# Transmitter_Schematic_Visualization.net
KiCad netlist of a schematic drawn in EAGLE
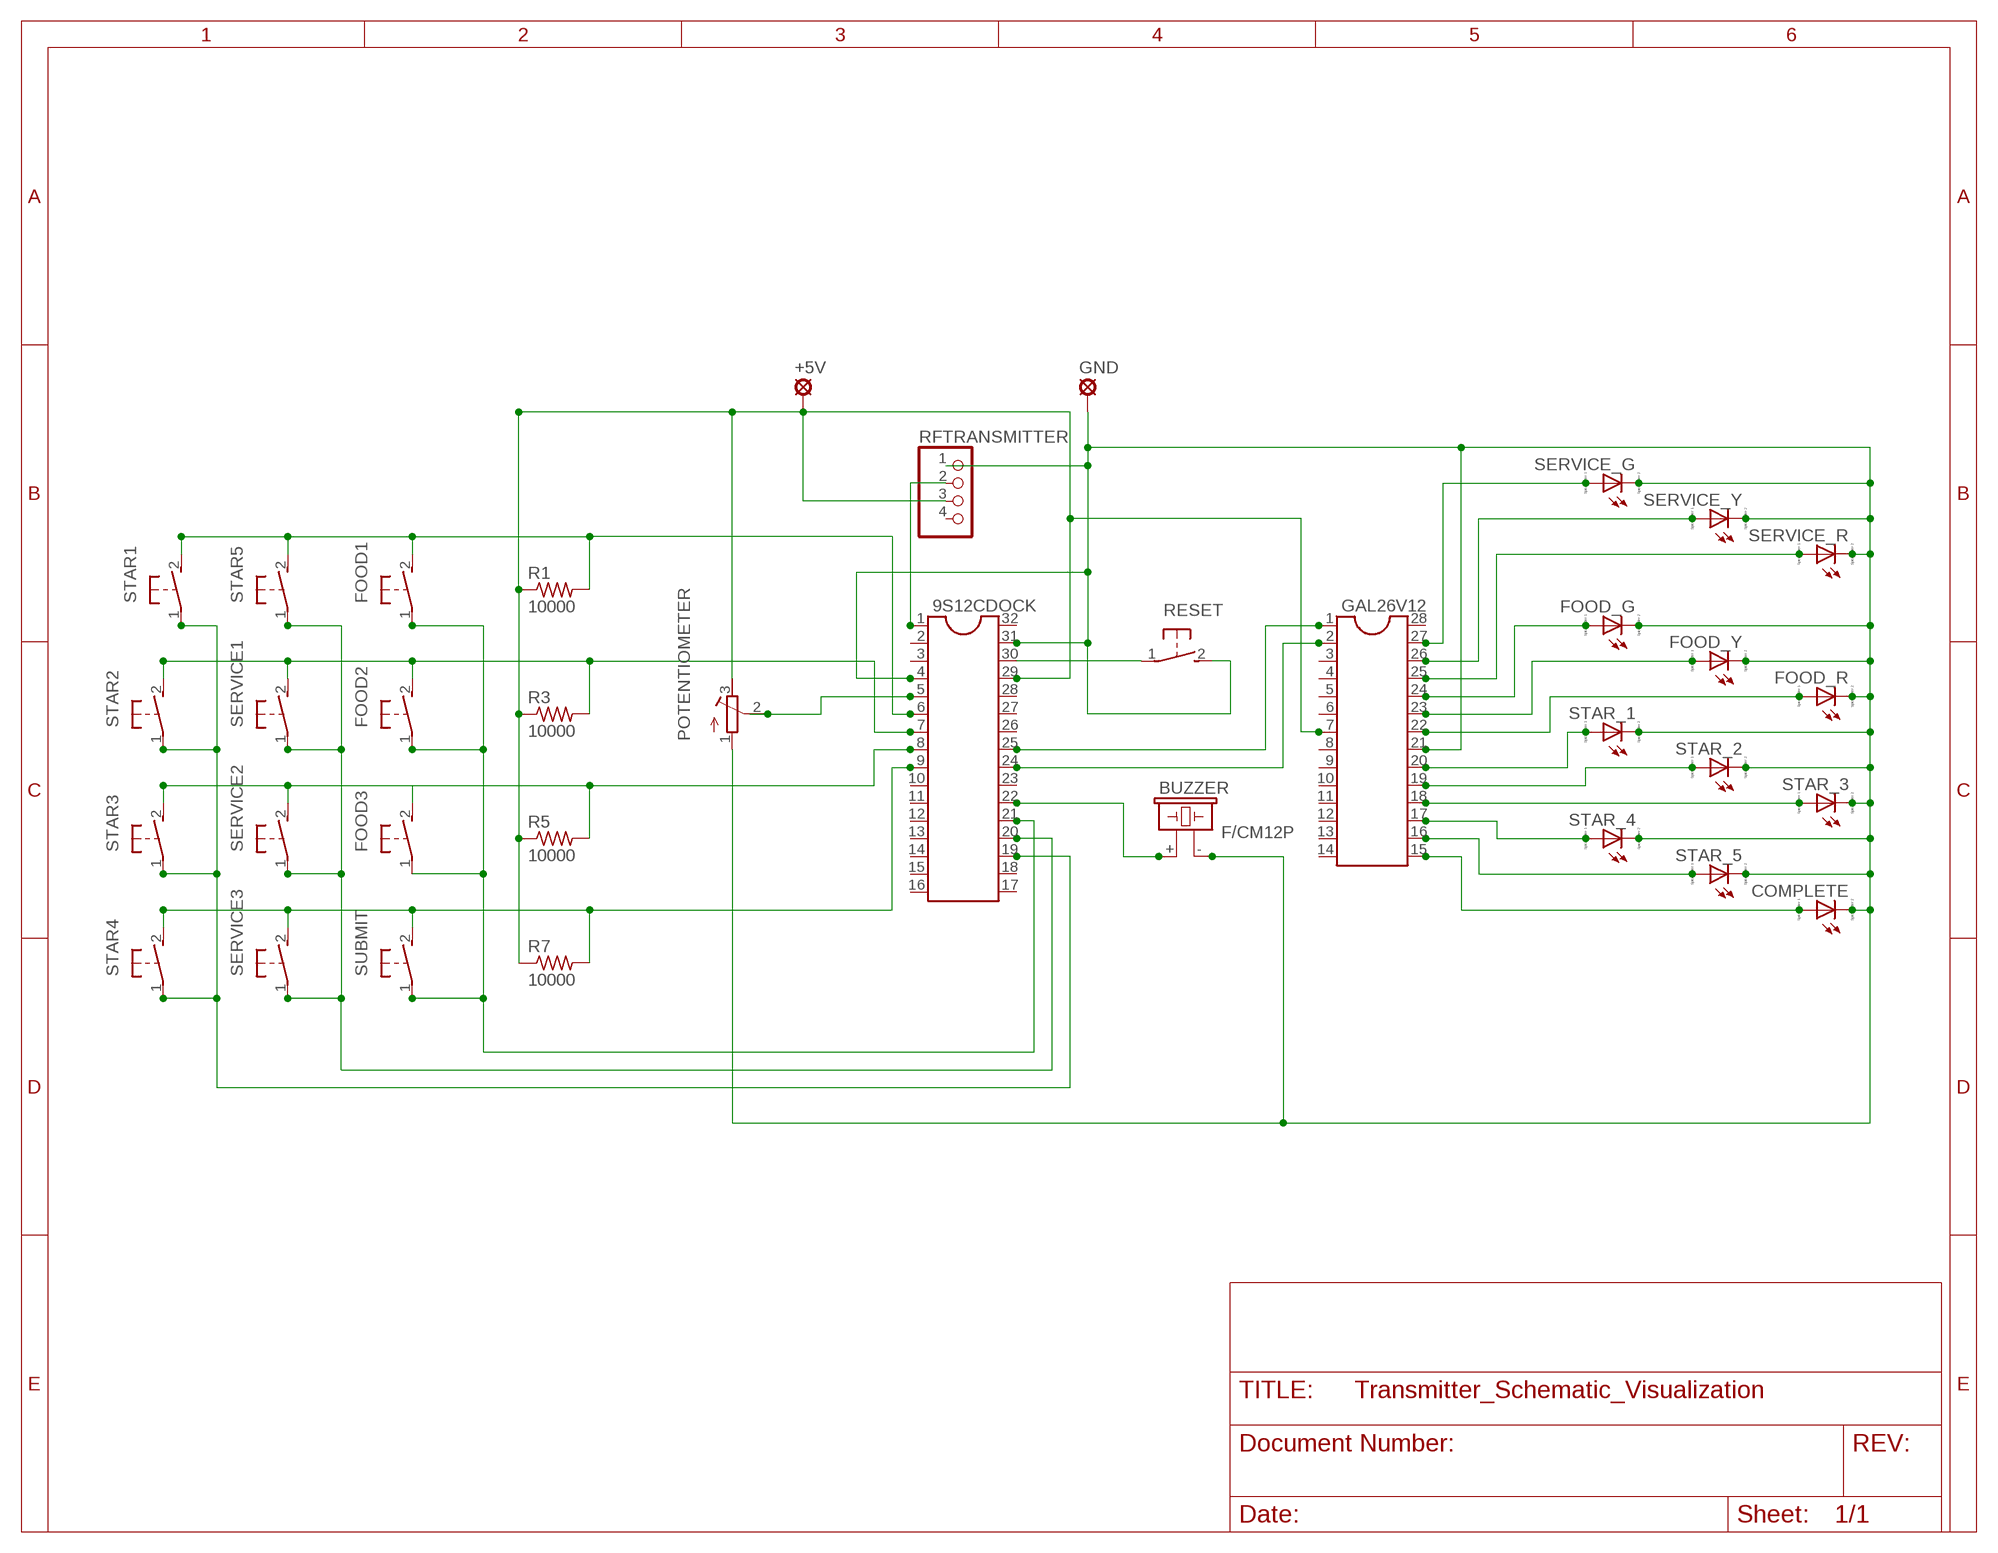
[diagram p0: schematic, sheet 1]

(export (version "E")
  (design (tool "Eeschema 10.0.6"))
  (components
    (comp (ref "+5V")
      (value "LSP10")
      (footprint "eagle-import:LSP10")
      (libsource (lib "eagle-import") (part "LSP10"))
    )
    (comp (ref "9S12CDOCK")
      (value "DIL32")
      (footprint "eagle-import:DIL32")
      (libsource (lib "eagle-import") (part "DIL32"))
    )
    (comp (ref "BUZZER")
      (value "F/CM12P")
      (footprint "eagle-import:F_CM12P")
      (libsource (lib "eagle-import") (part "F/CM12P"))
    )
    (comp (ref "COMPLETE")
      (value "LED_E")
      (footprint "eagle-import:LED_1206")
      (libsource (lib "eagle-import") (part "LED_E"))
    )
    (comp (ref "FOOD1")
      (value "31-XX")
      (footprint "eagle-import:B3F-31XX")
      (fields (field (name "MPN") "B3F-3100"))
      (libsource (lib "eagle-import") (part "31-XX"))
    )
    (comp (ref "FOOD2")
      (value "31-XX")
      (footprint "eagle-import:B3F-31XX")
      (fields (field (name "MPN") "B3F-3100"))
      (libsource (lib "eagle-import") (part "31-XX"))
    )
    (comp (ref "FOOD3")
      (value "31-XX")
      (footprint "eagle-import:B3F-31XX")
      (fields (field (name "MPN") "B3F-3100"))
      (libsource (lib "eagle-import") (part "31-XX"))
    )
    (comp (ref "FOOD_G")
      (value "LED_E")
      (footprint "eagle-import:LED_1206")
      (libsource (lib "eagle-import") (part "LED_E"))
    )
    (comp (ref "FOOD_R")
      (value "LED_E")
      (footprint "eagle-import:LED_1206")
      (libsource (lib "eagle-import") (part "LED_E"))
    )
    (comp (ref "FOOD_Y")
      (value "LED_E")
      (footprint "eagle-import:LED_1206")
      (libsource (lib "eagle-import") (part "LED_E"))
    )
    (comp (ref "GAL26V12")
      (value "DIL28")
      (footprint "eagle-import:DIL28-6")
      (libsource (lib "eagle-import") (part "DIL28"))
    )
    (comp (ref "GND")
      (value "LSP10")
      (footprint "eagle-import:LSP10")
      (libsource (lib "eagle-import") (part "LSP10"))
    )
    (comp (ref "POTENTIOMETER")
      (value "R-TRIMM3296X")
      (footprint "eagle-import:RTRIM3296X")
      (libsource (lib "eagle-import") (part "R-TRIMM3296X"))
    )
    (comp (ref "R1")
      (value "10000")
      (footprint "eagle-import:0204_5")
      (libsource (lib "eagle-import") (part "R-US_0204/5"))
    )
    (comp (ref "R3")
      (value "10000")
      (footprint "eagle-import:0204_5")
      (libsource (lib "eagle-import") (part "R-US_0204/5"))
    )
    (comp (ref "R5")
      (value "10000")
      (footprint "eagle-import:0204_5")
      (libsource (lib "eagle-import") (part "R-US_0204/5"))
    )
    (comp (ref "R7")
      (value "10000")
      (footprint "eagle-import:0204_5")
      (libsource (lib "eagle-import") (part "R-US_0204/5"))
    )
    (comp (ref "RESET")
      (value "31-XX")
      (footprint "eagle-import:B3F-31XX")
      (fields (field (name "MPN") "B3F-3100"))
      (libsource (lib "eagle-import") (part "31-XX"))
    )
    (comp (ref "RFTRANSMITTER")
      (value "PINHD-1X4")
      (footprint "eagle-import:1X04")
      (libsource (lib "eagle-import") (part "PINHD-1X4"))
    )
    (comp (ref "SERVICE1")
      (value "31-XX")
      (footprint "eagle-import:B3F-31XX")
      (fields (field (name "MPN") "B3F-3100"))
      (libsource (lib "eagle-import") (part "31-XX"))
    )
    (comp (ref "SERVICE2")
      (value "31-XX")
      (footprint "eagle-import:B3F-31XX")
      (fields (field (name "MPN") "B3F-3100"))
      (libsource (lib "eagle-import") (part "31-XX"))
    )
    (comp (ref "SERVICE3")
      (value "31-XX")
      (footprint "eagle-import:B3F-31XX")
      (fields (field (name "MPN") "B3F-3100"))
      (libsource (lib "eagle-import") (part "31-XX"))
    )
    (comp (ref "SERVICE_G")
      (value "LED_E")
      (footprint "eagle-import:LED_1206")
      (libsource (lib "eagle-import") (part "LED_E"))
    )
    (comp (ref "SERVICE_R")
      (value "LED_E")
      (footprint "eagle-import:LED_1206")
      (libsource (lib "eagle-import") (part "LED_E"))
    )
    (comp (ref "SERVICE_Y")
      (value "LED_E")
      (footprint "eagle-import:LED_1206")
      (libsource (lib "eagle-import") (part "LED_E"))
    )
    (comp (ref "STAR1")
      (value "31-XX")
      (footprint "eagle-import:B3F-31XX")
      (fields (field (name "MPN") "B3F-3100"))
      (libsource (lib "eagle-import") (part "31-XX"))
    )
    (comp (ref "STAR2")
      (value "31-XX")
      (footprint "eagle-import:B3F-31XX")
      (fields (field (name "MPN") "B3F-3100"))
      (libsource (lib "eagle-import") (part "31-XX"))
    )
    (comp (ref "STAR3")
      (value "31-XX")
      (footprint "eagle-import:B3F-31XX")
      (fields (field (name "MPN") "B3F-3100"))
      (libsource (lib "eagle-import") (part "31-XX"))
    )
    (comp (ref "STAR4")
      (value "31-XX")
      (footprint "eagle-import:B3F-31XX")
      (fields (field (name "MPN") "B3F-3100"))
      (libsource (lib "eagle-import") (part "31-XX"))
    )
    (comp (ref "STAR5")
      (value "31-XX")
      (footprint "eagle-import:B3F-31XX")
      (fields (field (name "MPN") "B3F-3100"))
      (libsource (lib "eagle-import") (part "31-XX"))
    )
    (comp (ref "STAR_1")
      (value "LED_E")
      (footprint "eagle-import:LED_1206")
      (libsource (lib "eagle-import") (part "LED_E"))
    )
    (comp (ref "STAR_2")
      (value "LED_E")
      (footprint "eagle-import:LED_1206")
      (libsource (lib "eagle-import") (part "LED_E"))
    )
    (comp (ref "STAR_3")
      (value "LED_E")
      (footprint "eagle-import:LED_1206")
      (libsource (lib "eagle-import") (part "LED_E"))
    )
    (comp (ref "STAR_4")
      (value "LED_E")
      (footprint "eagle-import:LED_1206")
      (libsource (lib "eagle-import") (part "LED_E"))
    )
    (comp (ref "STAR_5")
      (value "LED_E")
      (footprint "eagle-import:LED_1206")
      (libsource (lib "eagle-import") (part "LED_E"))
    )
    (comp (ref "SUBMIT")
      (value "31-XX")
      (footprint "eagle-import:B3F-31XX")
      (fields (field (name "MPN") "B3F-3100"))
      (libsource (lib "eagle-import") (part "31-XX"))
    )
  )
  (nets
    (net (code "1") (name "Net-(9S12CDOCK-Pad1)") (class "Default")
      (node (ref "9S12CDOCK") (pin "1") (pinfunction "1_1") (pintype "passive"))
      (node (ref "RFTRANSMITTER") (pin "2") (pinfunction "2_2") (pintype "passive"))
    )
    (net (code "2") (name "Net-(9S12CDOCK-Pad24)") (class "Default")
      (node (ref "9S12CDOCK") (pin "24") (pinfunction "24_24") (pintype "passive"))
      (node (ref "GAL26V12") (pin "2") (pinfunction "2_2") (pintype "passive"))
    )
    (net (code "3") (name "Net-(9S12CDOCK-Pad25)") (class "Default")
      (node (ref "9S12CDOCK") (pin "25") (pinfunction "25_25") (pintype "passive"))
      (node (ref "GAL26V12") (pin "1") (pinfunction "1_1") (pintype "passive"))
    )
    (net (code "4") (name "Net-(BUZZER-1)") (class "Default")
      (node (ref "9S12CDOCK") (pin "22") (pinfunction "22_22") (pintype "passive"))
      (node (ref "BUZZER") (pin "+") (pinfunction "1_+") (pintype "passive"))
    )
    (net (code "5") (name "Net-(BUZZER-2)") (class "Default")
      (node (ref "9S12CDOCK") (pin "31") (pinfunction "31_31") (pintype "passive"))
      (node (ref "9S12CDOCK") (pin "4") (pinfunction "4_4") (pintype "passive"))
      (node (ref "BUZZER") (pin "-") (pinfunction "2_-") (pintype "passive"))
      (node (ref "COMPLETE") (pin "C") (pinfunction "C_C") (pintype "passive"))
      (node (ref "FOOD_G") (pin "C") (pinfunction "C_C") (pintype "passive"))
      (node (ref "FOOD_R") (pin "C") (pinfunction "C_C") (pintype "passive"))
      (node (ref "FOOD_Y") (pin "C") (pinfunction "C_C") (pintype "passive"))
      (node (ref "GAL26V12") (pin "21") (pinfunction "21_21") (pintype "passive"))
      (node (ref "GND") (pin "MP") (pinfunction "MP_MP") (pintype "passive"))
      (node (ref "POTENTIOMETER") (pin "1") (pinfunction "E_1") (pintype "passive"))
      (node (ref "RESET") (pin "2") (pinfunction "S_2") (pintype "passive"))
      (node (ref "RFTRANSMITTER") (pin "1") (pinfunction "1_1") (pintype "passive"))
      (node (ref "SERVICE_G") (pin "C") (pinfunction "C_C") (pintype "passive"))
      (node (ref "SERVICE_R") (pin "C") (pinfunction "C_C") (pintype "passive"))
      (node (ref "SERVICE_Y") (pin "C") (pinfunction "C_C") (pintype "passive"))
      (node (ref "STAR_1") (pin "C") (pinfunction "C_C") (pintype "passive"))
      (node (ref "STAR_2") (pin "C") (pinfunction "C_C") (pintype "passive"))
      (node (ref "STAR_3") (pin "C") (pinfunction "C_C") (pintype "passive"))
      (node (ref "STAR_4") (pin "C") (pinfunction "C_C") (pintype "passive"))
      (node (ref "STAR_5") (pin "C") (pinfunction "C_C") (pintype "passive"))
    )
    (net (code "6") (name "Net-(COMPLETE-PadA)") (class "Default")
      (node (ref "COMPLETE") (pin "A") (pinfunction "A_A") (pintype "passive"))
      (node (ref "GAL26V12") (pin "15") (pinfunction "15_15") (pintype "passive"))
    )
    (net (code "7") (name "Net-(FOOD1-P)") (class "Default")
      (node (ref "9S12CDOCK") (pin "21") (pinfunction "21_21") (pintype "passive"))
      (node (ref "FOOD1") (pin "1") (pinfunction "P_1") (pintype "passive"))
      (node (ref "FOOD2") (pin "1") (pinfunction "P_1") (pintype "passive"))
      (node (ref "FOOD3") (pin "1") (pinfunction "P_1") (pintype "passive"))
      (node (ref "SUBMIT") (pin "1") (pinfunction "P_1") (pintype "passive"))
    )
    (net (code "8") (name "Net-(FOOD1-S)") (class "Default")
      (node (ref "9S12CDOCK") (pin "6") (pinfunction "6_6") (pintype "passive"))
      (node (ref "FOOD1") (pin "2") (pinfunction "S_2") (pintype "passive"))
      (node (ref "R1") (pin "2") (pinfunction "2_2") (pintype "passive"))
      (node (ref "STAR1") (pin "2") (pinfunction "S_2") (pintype "passive"))
      (node (ref "STAR5") (pin "2") (pinfunction "S_2") (pintype "passive"))
    )
    (net (code "9") (name "Net-(FOOD2-S)") (class "Default")
      (node (ref "9S12CDOCK") (pin "7") (pinfunction "7_7") (pintype "passive"))
      (node (ref "FOOD2") (pin "2") (pinfunction "S_2") (pintype "passive"))
      (node (ref "R3") (pin "2") (pinfunction "2_2") (pintype "passive"))
      (node (ref "SERVICE1") (pin "2") (pinfunction "S_2") (pintype "passive"))
      (node (ref "STAR2") (pin "2") (pinfunction "S_2") (pintype "passive"))
    )
    (net (code "10") (name "Net-(FOOD3-S)") (class "Default")
      (node (ref "9S12CDOCK") (pin "8") (pinfunction "8_8") (pintype "passive"))
      (node (ref "FOOD3") (pin "2") (pinfunction "S_2") (pintype "passive"))
      (node (ref "R5") (pin "2") (pinfunction "2_2") (pintype "passive"))
      (node (ref "SERVICE2") (pin "2") (pinfunction "S_2") (pintype "passive"))
      (node (ref "STAR3") (pin "2") (pinfunction "S_2") (pintype "passive"))
    )
    (net (code "11") (name "Net-(FOOD_G-PadA)") (class "Default")
      (node (ref "FOOD_G") (pin "A") (pinfunction "A_A") (pintype "passive"))
      (node (ref "GAL26V12") (pin "24") (pinfunction "24_24") (pintype "passive"))
    )
    (net (code "12") (name "Net-(FOOD_R-PadA)") (class "Default")
      (node (ref "FOOD_R") (pin "A") (pinfunction "A_A") (pintype "passive"))
      (node (ref "GAL26V12") (pin "22") (pinfunction "22_22") (pintype "passive"))
    )
    (net (code "13") (name "Net-(FOOD_Y-PadA)") (class "Default")
      (node (ref "FOOD_Y") (pin "A") (pinfunction "A_A") (pintype "passive"))
      (node (ref "GAL26V12") (pin "23") (pinfunction "23_23") (pintype "passive"))
    )
    (net (code "14") (name "Net-(GAL26V12-Pad16)") (class "Default")
      (node (ref "GAL26V12") (pin "16") (pinfunction "16_16") (pintype "passive"))
      (node (ref "STAR_5") (pin "A") (pinfunction "A_A") (pintype "passive"))
    )
    (net (code "15") (name "Net-(GAL26V12-Pad17)") (class "Default")
      (node (ref "GAL26V12") (pin "17") (pinfunction "17_17") (pintype "passive"))
      (node (ref "STAR_4") (pin "A") (pinfunction "A_A") (pintype "passive"))
    )
    (net (code "16") (name "Net-(GAL26V12-Pad18)") (class "Default")
      (node (ref "GAL26V12") (pin "18") (pinfunction "18_18") (pintype "passive"))
      (node (ref "STAR_3") (pin "A") (pinfunction "A_A") (pintype "passive"))
    )
    (net (code "17") (name "Net-(GAL26V12-Pad19)") (class "Default")
      (node (ref "GAL26V12") (pin "19") (pinfunction "19_19") (pintype "passive"))
      (node (ref "STAR_2") (pin "A") (pinfunction "A_A") (pintype "passive"))
    )
    (net (code "18") (name "Net-(GAL26V12-Pad20)") (class "Default")
      (node (ref "GAL26V12") (pin "20") (pinfunction "20_20") (pintype "passive"))
      (node (ref "STAR_1") (pin "A") (pinfunction "A_A") (pintype "passive"))
    )
    (net (code "19") (name "Net-(GAL26V12-Pad25)") (class "Default")
      (node (ref "GAL26V12") (pin "25") (pinfunction "25_25") (pintype "passive"))
      (node (ref "SERVICE_R") (pin "A") (pinfunction "A_A") (pintype "passive"))
    )
    (net (code "20") (name "Net-(GAL26V12-Pad26)") (class "Default")
      (node (ref "GAL26V12") (pin "26") (pinfunction "26_26") (pintype "passive"))
      (node (ref "SERVICE_Y") (pin "A") (pinfunction "A_A") (pintype "passive"))
    )
    (net (code "21") (name "Net-(GAL26V12-Pad27)") (class "Default")
      (node (ref "GAL26V12") (pin "27") (pinfunction "27_27") (pintype "passive"))
      (node (ref "SERVICE_G") (pin "A") (pinfunction "A_A") (pintype "passive"))
    )
    (net (code "22") (name "Net-(POTENTIOMETER-A)") (class "Default")
      (node (ref "+5V") (pin "MP") (pinfunction "MP_MP") (pintype "passive"))
      (node (ref "9S12CDOCK") (pin "29") (pinfunction "29_29") (pintype "passive"))
      (node (ref "GAL26V12") (pin "7") (pinfunction "7_7") (pintype "passive"))
      (node (ref "POTENTIOMETER") (pin "3") (pinfunction "A_3") (pintype "passive"))
      (node (ref "R1") (pin "1") (pinfunction "1_1") (pintype "passive"))
      (node (ref "R3") (pin "1") (pinfunction "1_1") (pintype "passive"))
      (node (ref "R5") (pin "1") (pinfunction "1_1") (pintype "passive"))
      (node (ref "R7") (pin "1") (pinfunction "1_1") (pintype "passive"))
      (node (ref "RFTRANSMITTER") (pin "3") (pinfunction "3_3") (pintype "passive"))
    )
    (net (code "23") (name "Net-(POTENTIOMETER-S)") (class "Default")
      (node (ref "9S12CDOCK") (pin "5") (pinfunction "5_5") (pintype "passive"))
      (node (ref "POTENTIOMETER") (pin "2") (pinfunction "S_2") (pintype "passive"))
    )
    (net (code "24") (name "Net-(RESET-P)") (class "Default")
      (node (ref "9S12CDOCK") (pin "30") (pinfunction "30_30") (pintype "passive"))
      (node (ref "RESET") (pin "1") (pinfunction "P_1") (pintype "passive"))
    )
    (net (code "25") (name "Net-(SERVICE1-P)") (class "Default")
      (node (ref "9S12CDOCK") (pin "20") (pinfunction "20_20") (pintype "passive"))
      (node (ref "SERVICE1") (pin "1") (pinfunction "P_1") (pintype "passive"))
      (node (ref "SERVICE2") (pin "1") (pinfunction "P_1") (pintype "passive"))
      (node (ref "SERVICE3") (pin "1") (pinfunction "P_1") (pintype "passive"))
      (node (ref "STAR5") (pin "1") (pinfunction "P_1") (pintype "passive"))
    )
    (net (code "26") (name "Net-(SERVICE3-S)") (class "Default")
      (node (ref "9S12CDOCK") (pin "9") (pinfunction "9_9") (pintype "passive"))
      (node (ref "R7") (pin "2") (pinfunction "2_2") (pintype "passive"))
      (node (ref "SERVICE3") (pin "2") (pinfunction "S_2") (pintype "passive"))
      (node (ref "STAR4") (pin "2") (pinfunction "S_2") (pintype "passive"))
      (node (ref "SUBMIT") (pin "2") (pinfunction "S_2") (pintype "passive"))
    )
    (net (code "27") (name "Net-(STAR1-P)") (class "Default")
      (node (ref "9S12CDOCK") (pin "19") (pinfunction "19_19") (pintype "passive"))
      (node (ref "STAR1") (pin "1") (pinfunction "P_1") (pintype "passive"))
      (node (ref "STAR2") (pin "1") (pinfunction "P_1") (pintype "passive"))
      (node (ref "STAR3") (pin "1") (pinfunction "P_1") (pintype "passive"))
      (node (ref "STAR4") (pin "1") (pinfunction "P_1") (pintype "passive"))
    )
    (net (code "28") (name "unconnected-(9S12CDOCK-Pad2)") (class "Default")
      (node (ref "9S12CDOCK") (pin "2") (pinfunction "2_2") (pintype "passive"))
    )
    (net (code "29") (name "unconnected-(9S12CDOCK-Pad3)") (class "Default")
      (node (ref "9S12CDOCK") (pin "3") (pinfunction "3_3") (pintype "passive"))
    )
    (net (code "30") (name "unconnected-(9S12CDOCK-Pad10)") (class "Default")
      (node (ref "9S12CDOCK") (pin "10") (pinfunction "10_10") (pintype "passive"))
    )
    (net (code "31") (name "unconnected-(9S12CDOCK-Pad11)") (class "Default")
      (node (ref "9S12CDOCK") (pin "11") (pinfunction "11_11") (pintype "passive"))
    )
    (net (code "32") (name "unconnected-(9S12CDOCK-Pad12)") (class "Default")
      (node (ref "9S12CDOCK") (pin "12") (pinfunction "12_12") (pintype "passive"))
    )
    (net (code "33") (name "unconnected-(9S12CDOCK-Pad13)") (class "Default")
      (node (ref "9S12CDOCK") (pin "13") (pinfunction "13_13") (pintype "passive"))
    )
    (net (code "34") (name "unconnected-(9S12CDOCK-Pad14)") (class "Default")
      (node (ref "9S12CDOCK") (pin "14") (pinfunction "14_14") (pintype "passive"))
    )
    (net (code "35") (name "unconnected-(9S12CDOCK-Pad15)") (class "Default")
      (node (ref "9S12CDOCK") (pin "15") (pinfunction "15_15") (pintype "passive"))
    )
    (net (code "36") (name "unconnected-(9S12CDOCK-Pad16)") (class "Default")
      (node (ref "9S12CDOCK") (pin "16") (pinfunction "16_16") (pintype "passive"))
    )
    (net (code "37") (name "unconnected-(9S12CDOCK-Pad17)") (class "Default")
      (node (ref "9S12CDOCK") (pin "17") (pinfunction "17_17") (pintype "passive"))
    )
    (net (code "38") (name "unconnected-(9S12CDOCK-Pad18)") (class "Default")
      (node (ref "9S12CDOCK") (pin "18") (pinfunction "18_18") (pintype "passive"))
    )
    (net (code "39") (name "unconnected-(9S12CDOCK-Pad23)") (class "Default")
      (node (ref "9S12CDOCK") (pin "23") (pinfunction "23_23") (pintype "passive"))
    )
    (net (code "40") (name "unconnected-(9S12CDOCK-Pad26)") (class "Default")
      (node (ref "9S12CDOCK") (pin "26") (pinfunction "26_26") (pintype "passive"))
    )
    (net (code "41") (name "unconnected-(9S12CDOCK-Pad27)") (class "Default")
      (node (ref "9S12CDOCK") (pin "27") (pinfunction "27_27") (pintype "passive"))
    )
    (net (code "42") (name "unconnected-(9S12CDOCK-Pad28)") (class "Default")
      (node (ref "9S12CDOCK") (pin "28") (pinfunction "28_28") (pintype "passive"))
    )
    (net (code "43") (name "unconnected-(9S12CDOCK-Pad32)") (class "Default")
      (node (ref "9S12CDOCK") (pin "32") (pinfunction "32_32") (pintype "passive"))
    )
    (net (code "44") (name "unconnected-(GAL26V12-Pad3)") (class "Default")
      (node (ref "GAL26V12") (pin "3") (pinfunction "3_3") (pintype "passive"))
    )
    (net (code "45") (name "unconnected-(GAL26V12-Pad4)") (class "Default")
      (node (ref "GAL26V12") (pin "4") (pinfunction "4_4") (pintype "passive"))
    )
    (net (code "46") (name "unconnected-(GAL26V12-Pad5)") (class "Default")
      (node (ref "GAL26V12") (pin "5") (pinfunction "5_5") (pintype "passive"))
    )
    (net (code "47") (name "unconnected-(GAL26V12-Pad6)") (class "Default")
      (node (ref "GAL26V12") (pin "6") (pinfunction "6_6") (pintype "passive"))
    )
    (net (code "48") (name "unconnected-(GAL26V12-Pad8)") (class "Default")
      (node (ref "GAL26V12") (pin "8") (pinfunction "8_8") (pintype "passive"))
    )
    (net (code "49") (name "unconnected-(GAL26V12-Pad9)") (class "Default")
      (node (ref "GAL26V12") (pin "9") (pinfunction "9_9") (pintype "passive"))
    )
    (net (code "50") (name "unconnected-(GAL26V12-Pad10)") (class "Default")
      (node (ref "GAL26V12") (pin "10") (pinfunction "10_10") (pintype "passive"))
    )
    (net (code "51") (name "unconnected-(GAL26V12-Pad11)") (class "Default")
      (node (ref "GAL26V12") (pin "11") (pinfunction "11_11") (pintype "passive"))
    )
    (net (code "52") (name "unconnected-(GAL26V12-Pad12)") (class "Default")
      (node (ref "GAL26V12") (pin "12") (pinfunction "12_12") (pintype "passive"))
    )
    (net (code "53") (name "unconnected-(GAL26V12-Pad13)") (class "Default")
      (node (ref "GAL26V12") (pin "13") (pinfunction "13_13") (pintype "passive"))
    )
    (net (code "54") (name "unconnected-(GAL26V12-Pad14)") (class "Default")
      (node (ref "GAL26V12") (pin "14") (pinfunction "14_14") (pintype "passive"))
    )
    (net (code "55") (name "unconnected-(GAL26V12-Pad28)") (class "Default")
      (node (ref "GAL26V12") (pin "28") (pinfunction "28_28") (pintype "passive"))
    )
    (net (code "56") (name "unconnected-(RFTRANSMITTER-Pad4)") (class "Default")
      (node (ref "RFTRANSMITTER") (pin "4") (pinfunction "4_4") (pintype "passive"))
    )
  )
)
